# TOPSHEET.net
KiCad netlist of a schematic drawn in Altium Designer
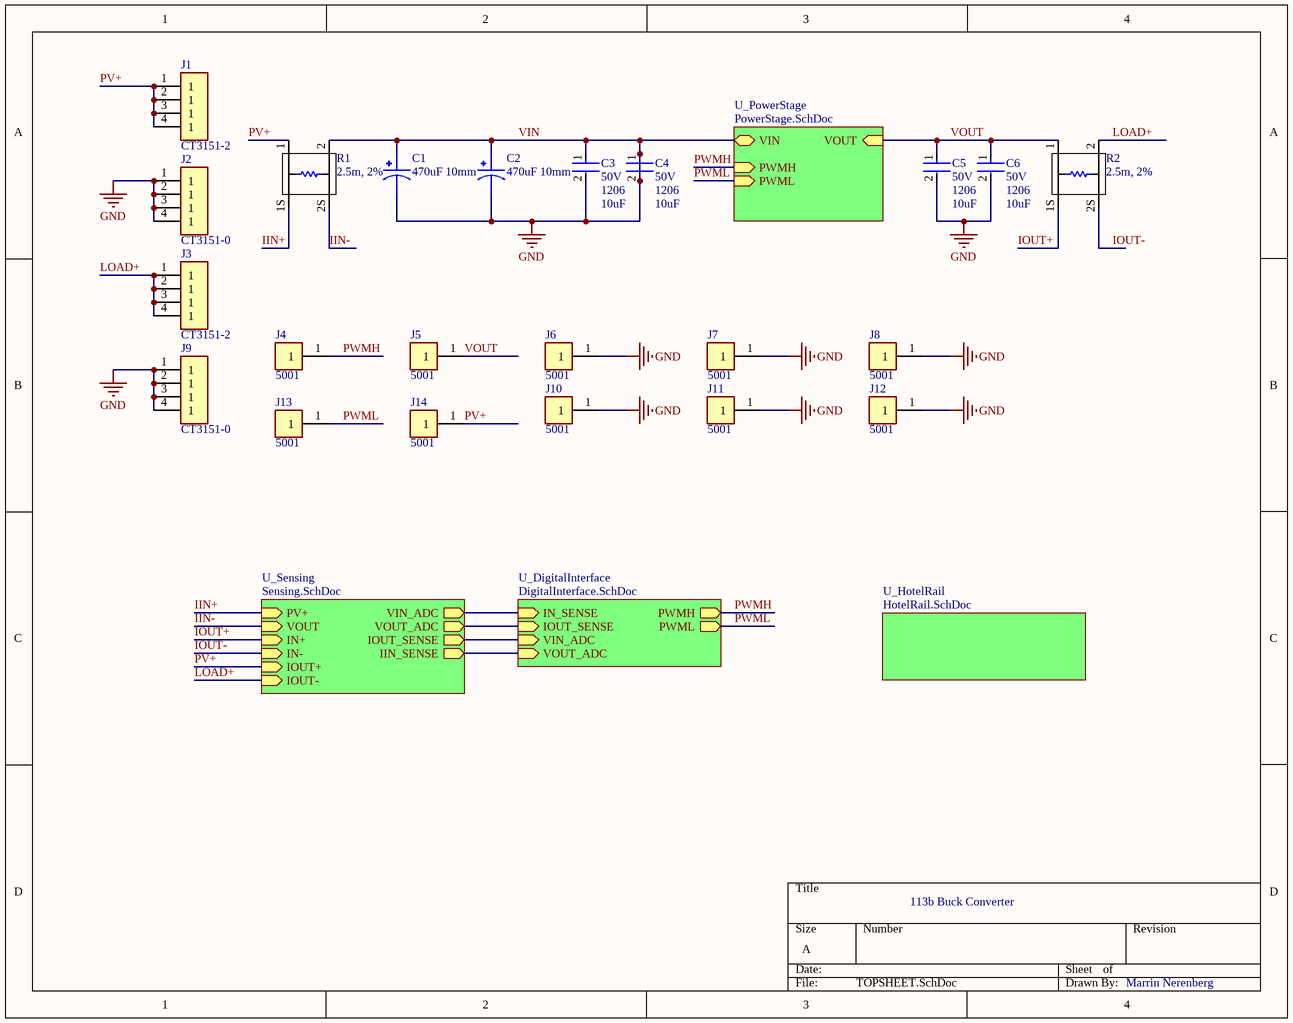
[diagram p0: TOPSHEET.SchDoc]

(export (version "E")
  (design (tool "Eeschema 10.0.6"))
  (components
    (comp (ref "C1")
      (value "470uF 10mm")
      (footprint "B41856C7477M000:CAPPRD500W60D1000H2200")
      (fields (field (name "MF") "{'manufacturer': u'EPCOS'}") (field (name "MP") "B41856C7477M000"))
      (libsource (lib "*") (part "B41856C7477M000"))
    )
    (comp (ref "C2")
      (value "470uF 10mm")
      (footprint "B41856C7477M000:CAPPRD500W60D1000H2200")
      (fields (field (name "MF") "{'manufacturer': u'EPCOS'}") (field (name "MP") "B41856C7477M000"))
      (libsource (lib "*") (part "B41856C7477M000"))
    )
    (comp (ref "C3")
      (value "12065C475KAT2A")
      (footprint "FP-1206-L_3_2_0_2-W_1_6_0-IPC_B")
      (description "CAP CER 4.7UF 50V X7R 1206")
      (fields
        (field (name "VOLTAGE RATING (DC)") "50V")
        (field (name "TOLERANCE") "10%")
        (field (name "CASE/PACKAGE") "1206")
        (field (name "CAPACITANCE") "10uF")
        (field (name "MANUFACTURER") "Kyocera AVX")
      )
      (libsource (lib "PV Buck v2 Lib") (part "CMP-2000-07581-3"))
    )
    (comp (ref "C4")
      (value "12065C475KAT2A")
      (footprint "FP-1206-L_3_2_0_2-W_1_6_0-IPC_B")
      (description "CAP CER 4.7UF 50V X7R 1206")
      (fields
        (field (name "VOLTAGE RATING (DC)") "50V")
        (field (name "TOLERANCE") "10%")
        (field (name "CASE/PACKAGE") "1206")
        (field (name "CAPACITANCE") "10uF")
        (field (name "MANUFACTURER") "Kyocera AVX")
      )
      (libsource (lib "PV Buck v2 Lib") (part "CMP-2000-07581-3"))
    )
    (comp (ref "C5")
      (value "12065C475KAT2A")
      (footprint "FP-1206-L_3_2_0_2-W_1_6_0-IPC_B")
      (description "CAP CER 4.7UF 50V X7R 1206")
      (fields
        (field (name "VOLTAGE RATING (DC)") "50V")
        (field (name "TOLERANCE") "10%")
        (field (name "CASE/PACKAGE") "1206")
        (field (name "CAPACITANCE") "10uF")
        (field (name "MANUFACTURER") "Kyocera AVX")
      )
      (libsource (lib "PV Buck v2 Lib") (part "CMP-2000-07581-3"))
    )
    (comp (ref "C6")
      (value "12065C475KAT2A")
      (footprint "FP-1206-L_3_2_0_2-W_1_6_0-IPC_B")
      (description "CAP CER 4.7UF 50V X7R 1206")
      (fields
        (field (name "VOLTAGE RATING (DC)") "50V")
        (field (name "TOLERANCE") "10%")
        (field (name "CASE/PACKAGE") "1206")
        (field (name "CAPACITANCE") "10uF")
        (field (name "MANUFACTURER") "Kyocera AVX")
      )
      (libsource (lib "PV Buck v2 Lib") (part "CMP-2000-07581-3"))
    )
    (comp (ref "J1")
      (value "CT3151-2")
      (footprint "CALTEST_CT3151-2")
      (description "Banana Jack Connector Standard Banana Solder Red")
      (fields (field (name "MF") "{'manufacturer': u'Cal Test'}"))
      (libsource (lib "PV Buck v2 Lib") (part "CT3151-2_1"))
    )
    (comp (ref "J2")
      (value "CT3151-0")
      (footprint "CT3151-0")
      (description "Banana Jack Connector Standard Banana Solder Red")
      (fields (field (name "MF") "{'manufacturer': u'Cal Test'}") (field (name "MP") "CT3151-2"))
      (libsource (lib "PV Buck v2 Lib") (part "CT3151-2"))
    )
    (comp (ref "J3")
      (value "CT3151-2")
      (footprint "CALTEST_CT3151-2")
      (description "Banana Jack Connector Standard Banana Solder Red")
      (fields (field (name "MF") "{'manufacturer': u'Cal Test'}"))
      (libsource (lib "PV Buck v2 Lib") (part "CT3151-2_1"))
    )
    (comp (ref "J4")
      (value "5001")
      (footprint "FP-5001-MFG")
      (description "PC TEST POINT MINIATURE BLACK")
      (fields (field (name "MANUFACTURER") "Keystone Electronics"))
      (libsource (lib "PV Buck v2 Lib") (part "CMP-2000-05181-2"))
    )
    (comp (ref "J5")
      (value "5001")
      (footprint "FP-5001-MFG")
      (description "PC TEST POINT MINIATURE BLACK")
      (fields (field (name "MANUFACTURER") "Keystone Electronics"))
      (libsource (lib "PV Buck v2 Lib") (part "CMP-2000-05181-2"))
    )
    (comp (ref "J6")
      (value "5001")
      (footprint "FP-5001-MFG")
      (description "PC TEST POINT MINIATURE BLACK")
      (fields (field (name "MANUFACTURER") "Keystone Electronics"))
      (libsource (lib "PV Buck v2 Lib") (part "CMP-2000-05181-2"))
    )
    (comp (ref "J7")
      (value "5001")
      (footprint "FP-5001-MFG")
      (description "PC TEST POINT MINIATURE BLACK")
      (fields (field (name "MANUFACTURER") "Keystone Electronics"))
      (libsource (lib "PV Buck v2 Lib") (part "CMP-2000-05181-2"))
    )
    (comp (ref "J8")
      (value "5001")
      (footprint "FP-5001-MFG")
      (description "PC TEST POINT MINIATURE BLACK")
      (fields (field (name "MANUFACTURER") "Keystone Electronics"))
      (libsource (lib "PV Buck v2 Lib") (part "CMP-2000-05181-2"))
    )
    (comp (ref "J9")
      (value "CT3151-0")
      (footprint "CT3151-0")
      (description "Banana Jack Connector Standard Banana Solder Red")
      (fields (field (name "MF") "{'manufacturer': u'Cal Test'}") (field (name "MP") "CT3151-2"))
      (libsource (lib "PV Buck v2 Lib") (part "CT3151-2"))
    )
    (comp (ref "J10")
      (value "5001")
      (footprint "FP-5001-MFG")
      (description "PC TEST POINT MINIATURE BLACK")
      (fields (field (name "MANUFACTURER") "Keystone Electronics"))
      (libsource (lib "PV Buck v2 Lib") (part "CMP-2000-05181-2"))
    )
    (comp (ref "J11")
      (value "5001")
      (footprint "FP-5001-MFG")
      (description "PC TEST POINT MINIATURE BLACK")
      (fields (field (name "MANUFACTURER") "Keystone Electronics"))
      (libsource (lib "PV Buck v2 Lib") (part "CMP-2000-05181-2"))
    )
    (comp (ref "J12")
      (value "5001")
      (footprint "FP-5001-MFG")
      (description "PC TEST POINT MINIATURE BLACK")
      (fields (field (name "MANUFACTURER") "Keystone Electronics"))
      (libsource (lib "PV Buck v2 Lib") (part "CMP-2000-05181-2"))
    )
    (comp (ref "J13")
      (value "5001")
      (footprint "FP-5001-MFG")
      (description "PC TEST POINT MINIATURE BLACK")
      (fields (field (name "MANUFACTURER") "Keystone Electronics"))
      (libsource (lib "PV Buck v2 Lib") (part "CMP-2000-05181-2"))
    )
    (comp (ref "J14")
      (value "5001")
      (footprint "FP-5001-MFG")
      (description "PC TEST POINT MINIATURE BLACK")
      (fields (field (name "MANUFACTURER") "Keystone Electronics"))
      (libsource (lib "PV Buck v2 Lib") (part "CMP-2000-05181-2"))
    )
    (comp (ref "R1")
      (value "2.5m, 2%")
      (footprint "OHMITE_FC4L32")
      (description "2m, 0612, 2%, 1W")
      (fields (field (name "MFG") "Ohmite") (field (name "TOLERANCE") "2%"))
      (libsource (lib "PV Buck v2 Lib") (part "FC4L32R002GER"))
    )
    (comp (ref "R2")
      (value "2.5m, 2%")
      (footprint "OHMITE_FC4L32")
      (description "2m, 0612, 2%, 1W")
      (fields (field (name "MFG") "Ohmite") (field (name "TOLERANCE") "2%"))
      (libsource (lib "PV Buck v2 Lib") (part "FC4L32R002GER"))
    )
  )
  (nets
    (net (code "1") (name "/IIN+") (class "Default")
      (node (ref "R1") (pin "1S") (pinfunction "1S_1S") (pintype "passive"))
    )
    (net (code "2") (name "/IIN-") (class "Default")
      (node (ref "R1") (pin "2S") (pinfunction "2S_2S") (pintype "passive"))
    )
    (net (code "4") (name "/IOUT+") (class "Default")
      (node (ref "R2") (pin "1S") (pinfunction "1S_1S") (pintype "passive"))
    )
    (net (code "5") (name "/IOUT-") (class "Default")
      (node (ref "R2") (pin "2S") (pinfunction "2S_2S") (pintype "passive"))
    )
    (net (code "7") (name "/LOAD+") (class "Default")
      (node (ref "J3") (pin "1") (pinfunction "1_1") (pintype "passive"))
      (node (ref "J3") (pin "2") (pinfunction "1_2") (pintype "passive"))
      (node (ref "J3") (pin "3") (pinfunction "1_3") (pintype "passive"))
      (node (ref "J3") (pin "4") (pinfunction "1_4") (pintype "passive"))
      (node (ref "R2") (pin "2") (pinfunction "2_2") (pintype "passive"))
    )
    (net (code "8") (name "/PV+") (class "Default")
      (node (ref "J1") (pin "1") (pinfunction "1_1") (pintype "passive"))
      (node (ref "J1") (pin "2") (pinfunction "1_2") (pintype "passive"))
      (node (ref "J1") (pin "3") (pinfunction "1_3") (pintype "passive"))
      (node (ref "J1") (pin "4") (pinfunction "1_4") (pintype "passive"))
      (node (ref "J14") (pin "1") (pinfunction "1_1") (pintype "passive"))
      (node (ref "R1") (pin "1") (pinfunction "1_1") (pintype "passive"))
    )
    (net (code "9") (name "/PWMH") (class "Default")
      (node (ref "J4") (pin "1") (pinfunction "1_1") (pintype "passive"))
    )
    (net (code "10") (name "/PWML") (class "Default")
      (node (ref "J13") (pin "1") (pinfunction "1_1") (pintype "passive"))
    )
    (net (code "12") (name "/VOUT") (class "Default")
      (node (ref "C5") (pin "1") (pinfunction "1_1") (pintype "passive"))
      (node (ref "C6") (pin "1") (pinfunction "1_1") (pintype "passive"))
      (node (ref "J5") (pin "1") (pinfunction "1_1") (pintype "passive"))
      (node (ref "R2") (pin "1") (pinfunction "1_1") (pintype "passive"))
    )
    (net (code "14") (name "GND") (class "Default")
      (node (ref "C1") (pin "1") (pinfunction "1_1") (pintype "passive"))
      (node (ref "C1") (pin "2") (pinfunction "2_2") (pintype "passive"))
      (node (ref "C2") (pin "1") (pinfunction "1_1") (pintype "passive"))
      (node (ref "C2") (pin "2") (pinfunction "2_2") (pintype "passive"))
      (node (ref "C3") (pin "1") (pinfunction "1_1") (pintype "passive"))
      (node (ref "C3") (pin "2") (pinfunction "2_2") (pintype "passive"))
      (node (ref "C4") (pin "1") (pinfunction "1_1") (pintype "passive"))
      (node (ref "C4") (pin "2") (pinfunction "2_2") (pintype "passive"))
      (node (ref "C5") (pin "2") (pinfunction "2_2") (pintype "passive"))
      (node (ref "C6") (pin "2") (pinfunction "2_2") (pintype "passive"))
      (node (ref "J10") (pin "1") (pinfunction "1_1") (pintype "passive"))
      (node (ref "J11") (pin "1") (pinfunction "1_1") (pintype "passive"))
      (node (ref "J12") (pin "1") (pinfunction "1_1") (pintype "passive"))
      (node (ref "J2") (pin "1") (pinfunction "1_1") (pintype "passive"))
      (node (ref "J2") (pin "2") (pinfunction "1_2") (pintype "passive"))
      (node (ref "J2") (pin "3") (pinfunction "1_3") (pintype "passive"))
      (node (ref "J2") (pin "4") (pinfunction "1_4") (pintype "passive"))
      (node (ref "J6") (pin "1") (pinfunction "1_1") (pintype "passive"))
      (node (ref "J7") (pin "1") (pinfunction "1_1") (pintype "passive"))
      (node (ref "J8") (pin "1") (pinfunction "1_1") (pintype "passive"))
      (node (ref "J9") (pin "1") (pinfunction "1_1") (pintype "passive"))
      (node (ref "J9") (pin "2") (pinfunction "1_2") (pintype "passive"))
      (node (ref "J9") (pin "3") (pinfunction "1_3") (pintype "passive"))
      (node (ref "J9") (pin "4") (pinfunction "1_4") (pintype "passive"))
      (node (ref "R1") (pin "2") (pinfunction "2_2") (pintype "passive"))
    )
  )
)
